# POLL.net
KiCad netlist of a schematic drawn in Altium Designer
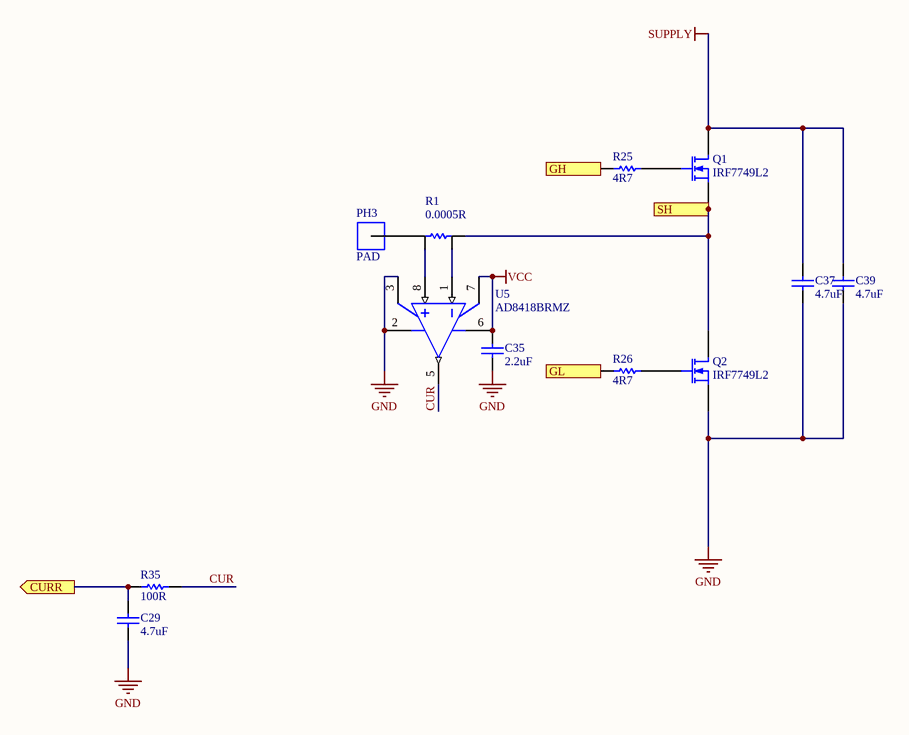
[diagram p0: POLL.SchDoc]

(export (version "E")
  (design (tool "Eeschema 10.0.6"))
  (components
    (comp (ref "C29")
      (value "4.7uF")
      (footprint "C0603[1608X92]")
      (description "4.7uF 6.3V 10% 0603 (1608 Metric)")
      (fields (field (name "PARTNUMBER") "GRM188R60J475KE19D") (field (name "MANUFACTURER") "Murata"))
      (libsource (lib "Capacitors") (part "CAP_4.7uF_6.3V_0603_10%"))
    )
    (comp (ref "C35")
      (value "2.2uF")
      (footprint "C0603[1608X92]")
      (description "2.2uF 6.3V 10% 0603 (1608 Metric)")
      (fields (field (name "PARTNUMBER") "GRM185R60J225KE26D") (field (name "MANUFACTURER") "Murata"))
      (libsource (lib "Capacitors") (part "CAP_2.2uF_6.3V_0603_10%"))
    )
    (comp (ref "C37")
      (value "4.7uF")
      (footprint "C1210[3225X200]")
      (description "4.7uF 100V 10% 1210 (3225 Metric)")
      (fields (field (name "PARTNUMBER") "GRJ32DC72A475KE11L") (field (name "MANUFACTURER") "Murata"))
      (libsource (lib "Capacitors") (part "CAP_4.7uF_100V_1210_10%"))
    )
    (comp (ref "C39")
      (value "4.7uF")
      (footprint "C1210[3225X200]")
      (description "4.7uF 100V 10% 1210 (3225 Metric)")
      (fields (field (name "PARTNUMBER") "GRJ32DC72A475KE11L") (field (name "MANUFACTURER") "Murata"))
      (libsource (lib "Capacitors") (part "CAP_4.7uF_100V_1210_10%"))
    )
    (comp (ref "PH3") (value "PAD") (footprint "PAD") (libsource (lib "Component") (part "PAD")))
    (comp (ref "Q1")
      (value "IRF7749L2")
      (footprint "DIRECTFET-9")
      (description "N-Channel MOSFET")
      (fields
        (field (name "PARTNUMBER") "IRF7749L1TRPBF")
        (field (name "MANUFACTURER") "Infineon Technologies")
      )
      (libsource (lib "MOSFETs") (part "IRF7749L2"))
    )
    (comp (ref "Q2")
      (value "IRF7749L2")
      (footprint "DIRECTFET-9")
      (description "N-Channel MOSFET")
      (fields
        (field (name "PARTNUMBER") "IRF7749L1TRPBF")
        (field (name "MANUFACTURER") "Infineon Technologies")
      )
      (libsource (lib "MOSFETs") (part "IRF7749L2"))
    )
    (comp (ref "R1")
      (value "0.0005R")
      (footprint "LRMAP3920B")
      (description "Current Sense Resistor, 0.0005R")
      (fields (field (name "PARTNUMBER") "LRMAP3920B") (field (name "MANUFACTURER") "IRC / TT Electronics"))
      (libsource (lib "Resistors") (part "LRMAP3920B"))
    )
    (comp (ref "R25")
      (value "4R7")
      (footprint "R0603[1608]")
      (description "4R7 0.25W 1% 0603 (1005 Metric)")
      (fields (field (name "MANUFACTURER") "Vishay / Dale") (field (name "PARTNUMBER") "CRCW06034R70JNEAHP"))
      (libsource (lib "Resistors") (part "RES_4R7_0603_1%"))
    )
    (comp (ref "R26")
      (value "4R7")
      (footprint "R0603[1608]")
      (description "4R7 0.25W 1% 0603 (1005 Metric)")
      (fields (field (name "MANUFACTURER") "Vishay / Dale") (field (name "PARTNUMBER") "CRCW06034R70JNEAHP"))
      (libsource (lib "Resistors") (part "RES_4R7_0603_1%"))
    )
    (comp (ref "R35")
      (value "100R")
      (footprint "R0603[1608]")
      (description "100R 0.25W 1% 0603 (1005 Metric)")
      (fields (field (name "MANUFACTURER") "Vishay / Dale") (field (name "PARTNUMBER") "CRCW0603100RFKEAHP"))
      (libsource (lib "Resistors") (part "RES_100R_0603_1%"))
    )
    (comp (ref "U5")
      (value "AD8418BRMZ")
      (footprint "MSOP-8")
      (description "Current Sense Amplifiers Zero Drift ,Precision Current Sense AMP")
      (fields (field (name "MANUFACTURER") "Analog Devices"))
      (libsource (lib "ICs") (part "AD8418BRMZ"))
    )
  )
  (nets
    (net (code "1") (name "/CUR") (class "Default")
      (node (ref "R35") (pin "2") (pinfunction "2_2") (pintype "passive"))
      (node (ref "U5") (pin "5") (pinfunction "OUT_5") (pintype "output"))
    )
    (net (code "2") (name "/CURR") (class "Default")
      (node (ref "C29") (pin "2") (pinfunction "2_2") (pintype "passive"))
      (node (ref "R35") (pin "1") (pinfunction "1_1") (pintype "passive"))
    )
    (net (code "3") (name "/GH") (class "Default")
      (node (ref "R25") (pin "1") (pinfunction "1_1") (pintype "passive"))
    )
    (net (code "4") (name "/GL") (class "Default")
      (node (ref "R26") (pin "1") (pinfunction "1_1") (pintype "passive"))
    )
    (net (code "5") (name "/SH") (class "Default")
      (node (ref "Q1") (pin "2") (pinfunction "S_2") (pintype "passive"))
      (node (ref "Q2") (pin "3") (pinfunction "D_3") (pintype "passive"))
      (node (ref "R1") (pin "2") (pinfunction "2_2") (pintype "passive"))
    )
    (net (code "6") (name "GND") (class "Default")
      (node (ref "C29") (pin "1") (pinfunction "1_1") (pintype "passive"))
      (node (ref "C35") (pin "2") (pinfunction "2_2") (pintype "passive"))
      (node (ref "C37") (pin "1") (pinfunction "1_1") (pintype "passive"))
      (node (ref "C39") (pin "1") (pinfunction "1_1") (pintype "passive"))
      (node (ref "Q2") (pin "2") (pinfunction "S_2") (pintype "passive"))
      (node (ref "U5") (pin "2") (pinfunction "GND_2") (pintype "power_in"))
      (node (ref "U5") (pin "3") (pinfunction "VREF2_3") (pintype "passive"))
    )
    (net (code "7") (name "Net-(PH3-PH)") (class "Default")
      (node (ref "PH3") (pin "0") (pinfunction "PH_0") (pintype "passive"))
      (node (ref "R1") (pin "1") (pinfunction "1_1") (pintype "passive"))
    )
    (net (code "8") (name "Net-(Q1-G)") (class "Default")
      (node (ref "Q1") (pin "1") (pinfunction "G_1") (pintype "passive"))
      (node (ref "R25") (pin "2") (pinfunction "2_2") (pintype "passive"))
    )
    (net (code "9") (name "Net-(Q2-G)") (class "Default")
      (node (ref "Q2") (pin "1") (pinfunction "G_1") (pintype "passive"))
      (node (ref "R26") (pin "2") (pinfunction "2_2") (pintype "passive"))
    )
    (net (code "10") (name "Net-(U5-IN+)") (class "Default")
      (node (ref "R1") (pin "3") (pinfunction "3_3") (pintype "passive"))
      (node (ref "U5") (pin "8") (pinfunction "IN+_8") (pintype "input"))
    )
    (net (code "11") (name "Net-(U5-IN-)") (class "Default")
      (node (ref "R1") (pin "4") (pinfunction "4_4") (pintype "passive"))
      (node (ref "U5") (pin "1") (pinfunction "IN-_1") (pintype "input"))
    )
    (net (code "12") (name "SUPPLY") (class "Default")
      (node (ref "C37") (pin "2") (pinfunction "2_2") (pintype "passive"))
      (node (ref "C39") (pin "2") (pinfunction "2_2") (pintype "passive"))
      (node (ref "Q1") (pin "3") (pinfunction "D_3") (pintype "passive"))
    )
    (net (code "13") (name "VCC") (class "Default")
      (node (ref "C35") (pin "1") (pinfunction "1_1") (pintype "passive"))
      (node (ref "U5") (pin "6") (pinfunction "VS_6") (pintype "power_in"))
      (node (ref "U5") (pin "7") (pinfunction "VREF1_7") (pintype "passive"))
    )
  )
)
